# SaidasMotoresCC.net
KiCad netlist of a schematic drawn in Altium Designer
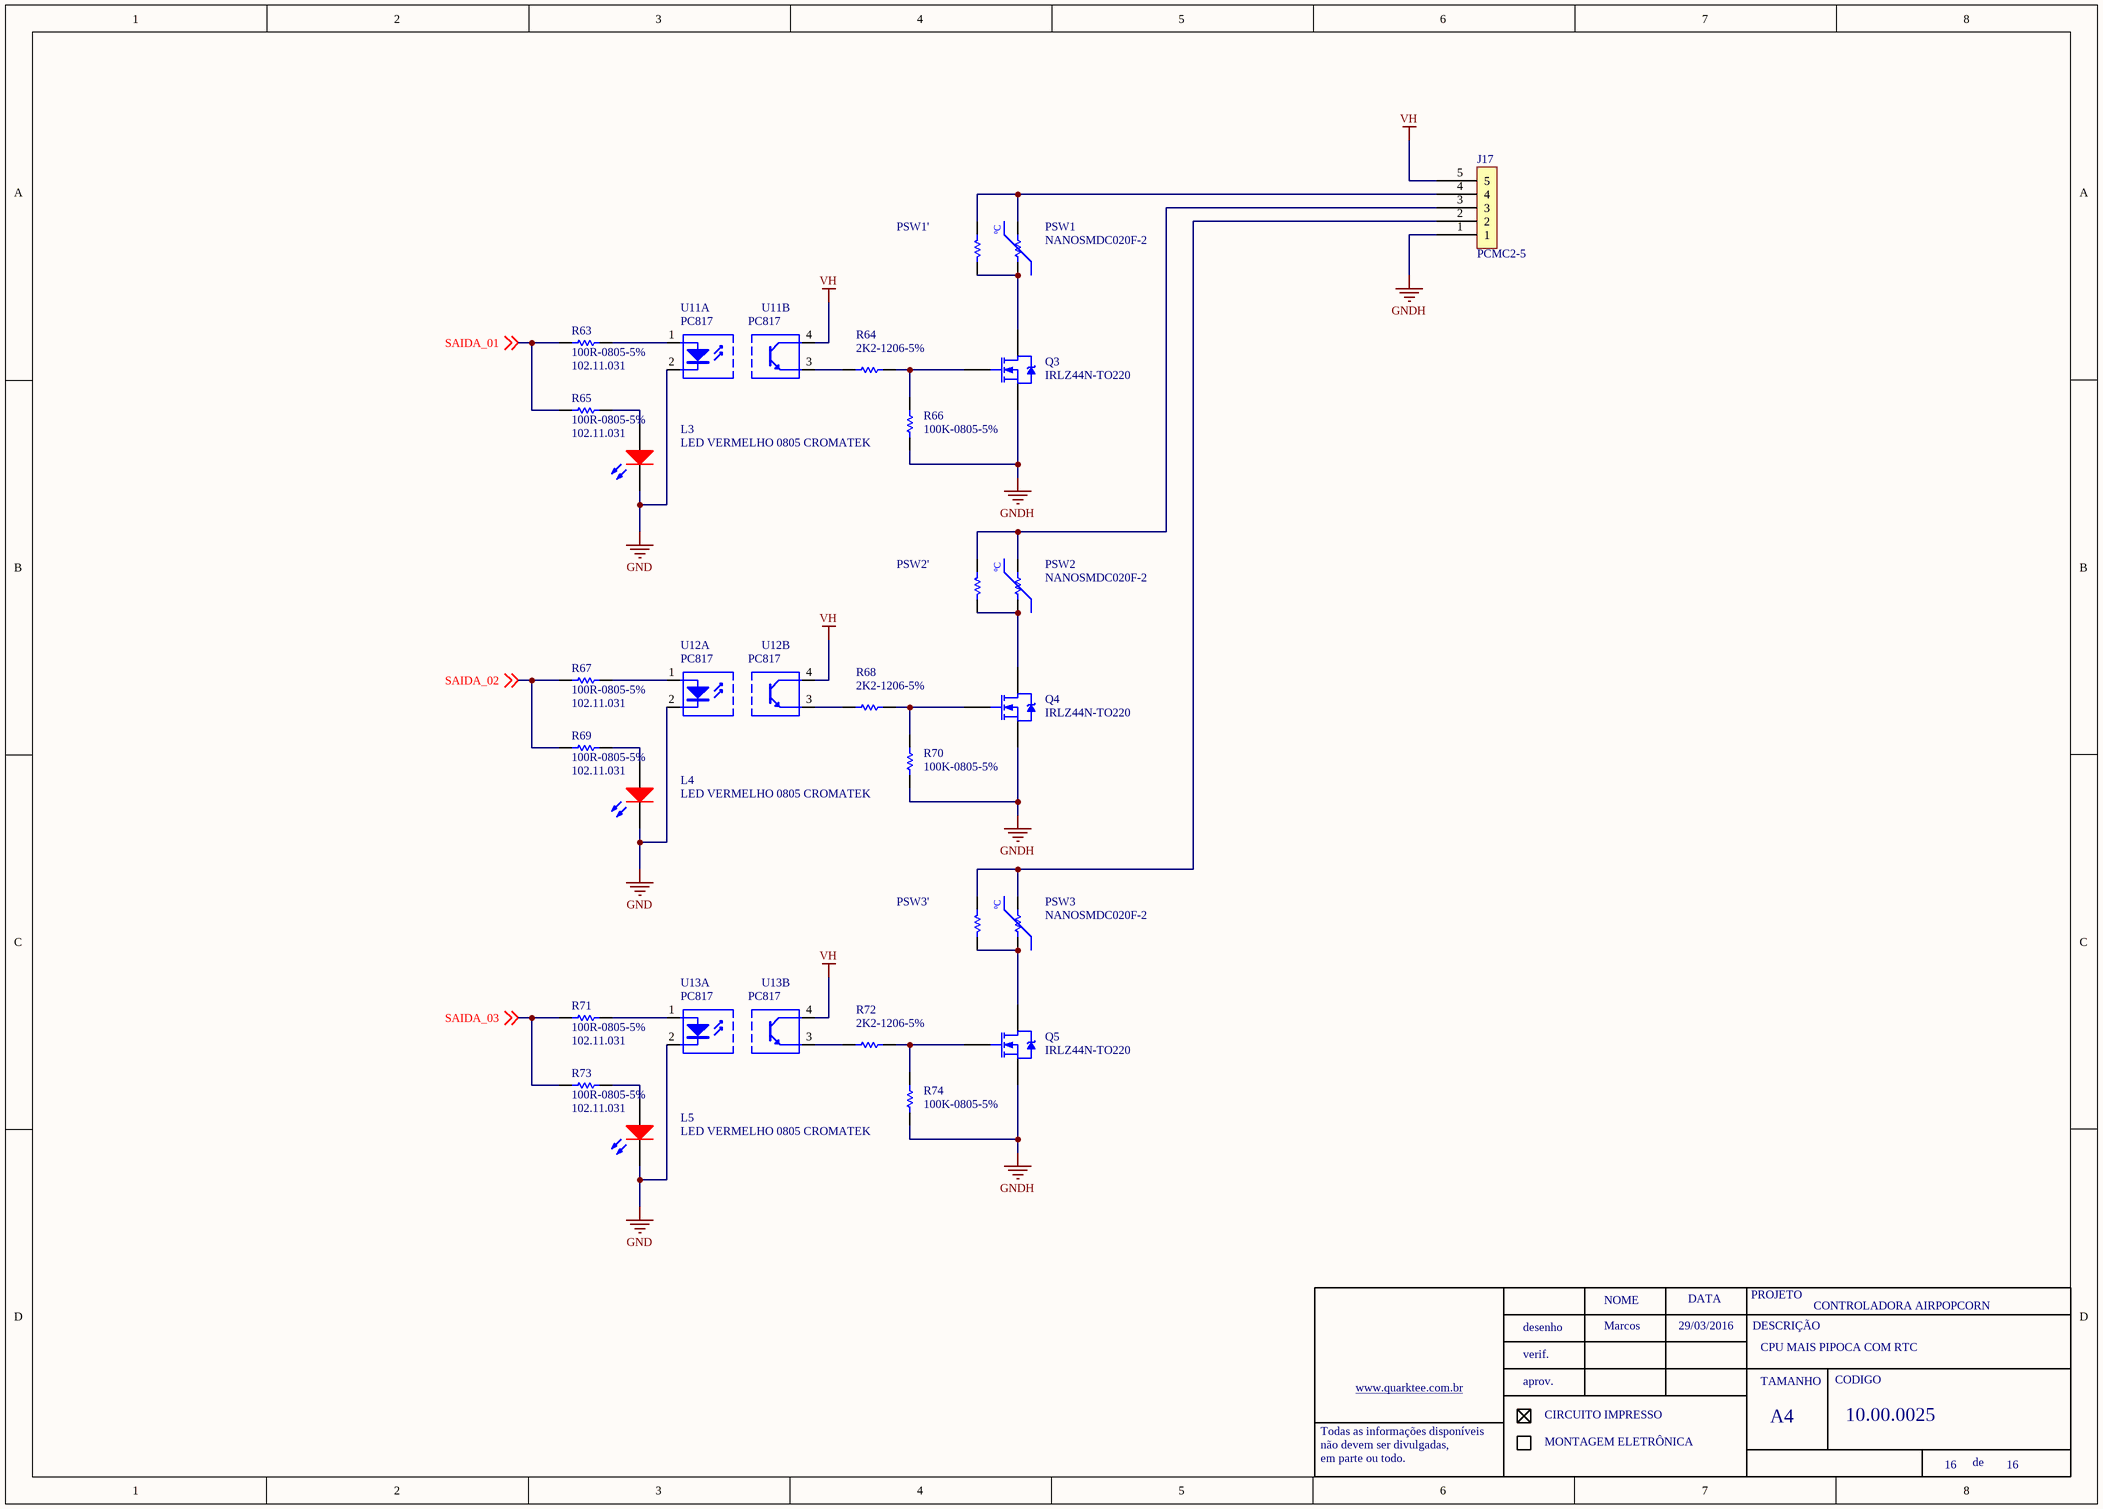
[diagram p0: SaidasMotoresCC.SchDoc]

(export (version "E")
  (design (tool "Eeschema 10.0.6"))
  (components
    (comp (ref "J17") (value "PCMC2-5") (footprint "PCMC2-5") (libsource (lib "AquinoLib") (part "PCMC2-5")))
    (comp (ref "L3")
      (value "LED VERMELHO 0805 CROMATEK")
      (footprint "LED 0805 - REVI")
      (description "LED VERMELHO 0603 SMD")
      (libsource (lib "AquinoLib") (part "LED VERMELHO 0603 SMD"))
    )
    (comp (ref "L4")
      (value "LED VERMELHO 0805 CROMATEK")
      (footprint "LED 0805 - REVI")
      (description "LED VERMELHO 0603 SMD")
      (libsource (lib "AquinoLib") (part "LED VERMELHO 0603 SMD"))
    )
    (comp (ref "L5")
      (value "LED VERMELHO 0805 CROMATEK")
      (footprint "LED 0805 - REVI")
      (description "LED VERMELHO 0603 SMD")
      (libsource (lib "AquinoLib") (part "LED VERMELHO 0603 SMD"))
    )
    (comp (ref "PSW1")
      (value "NANOSMDC020F-2")
      (footprint "2512 - REVISADO")
      (libsource (lib "AquinoLib") (part "POLYSWITCH 200mA"))
    )
    (comp (ref "PSW1'")
      (value "~")
      (footprint "1206-REVISADO O")
      (description "100K-0805-5%")
      (libsource (lib "AquinoLib") (part "100K-0805-5%"))
    )
    (comp (ref "PSW2")
      (value "NANOSMDC020F-2")
      (footprint "2512 - REVISADO")
      (libsource (lib "AquinoLib") (part "POLYSWITCH 200mA"))
    )
    (comp (ref "PSW2'")
      (value "~")
      (footprint "1206-REVISADO O")
      (description "100K-0805-5%")
      (libsource (lib "AquinoLib") (part "100K-0805-5%"))
    )
    (comp (ref "PSW3")
      (value "NANOSMDC020F-2")
      (footprint "2512 - REVISADO")
      (libsource (lib "AquinoLib") (part "POLYSWITCH 200mA"))
    )
    (comp (ref "PSW3'")
      (value "~")
      (footprint "1206-REVISADO O")
      (description "100K-0805-5%")
      (libsource (lib "AquinoLib") (part "100K-0805-5%"))
    )
    (comp (ref "Q3")
      (value "IRLZ44N-TO220")
      (footprint "TO220-3 EM PÉ")
      (libsource (lib "ChaveDigital3") (part "IRLZ44N-TO220"))
    )
    (comp (ref "Q4")
      (value "IRLZ44N-TO220")
      (footprint "TO220-3 EM PÉ")
      (libsource (lib "ChaveDigital3") (part "IRLZ44N-TO220"))
    )
    (comp (ref "Q5")
      (value "IRLZ44N-TO220")
      (footprint "TO220-3 EM PÉ")
      (libsource (lib "ChaveDigital3") (part "IRLZ44N-TO220"))
    )
    (comp (ref "R63")
      (value "100R-0805-5%")
      (footprint "0805-REVISADO O")
      (fields (field (name "ERP") "102.11.031"))
      (libsource (lib "AquinoLib") (part "100R-0805-5%"))
    )
    (comp (ref "R64")
      (value "2K2-1206-5%")
      (footprint "1206-REVISADO O")
      (description "100K-0805-5%")
      (libsource (lib "AquinoLib") (part "100K-0805-5%"))
    )
    (comp (ref "R65")
      (value "100R-0805-5%")
      (footprint "0805-REVISADO O")
      (fields (field (name "ERP") "102.11.031"))
      (libsource (lib "AquinoLib") (part "100R-0805-5%"))
    )
    (comp (ref "R66")
      (value "100K-0805-5%")
      (footprint "0805-REVISADO O")
      (libsource (lib "AquinoLib") (part "100K-0805-5%"))
    )
    (comp (ref "R67")
      (value "100R-0805-5%")
      (footprint "0805-REVISADO O")
      (fields (field (name "ERP") "102.11.031"))
      (libsource (lib "AquinoLib") (part "100R-0805-5%"))
    )
    (comp (ref "R68")
      (value "2K2-1206-5%")
      (footprint "1206-REVISADO O")
      (description "100K-0805-5%")
      (libsource (lib "AquinoLib") (part "100K-0805-5%"))
    )
    (comp (ref "R69")
      (value "100R-0805-5%")
      (footprint "0805-REVISADO O")
      (fields (field (name "ERP") "102.11.031"))
      (libsource (lib "AquinoLib") (part "100R-0805-5%"))
    )
    (comp (ref "R70")
      (value "100K-0805-5%")
      (footprint "0805-REVISADO O")
      (libsource (lib "AquinoLib") (part "100K-0805-5%"))
    )
    (comp (ref "R71")
      (value "100R-0805-5%")
      (footprint "0805-REVISADO O")
      (fields (field (name "ERP") "102.11.031"))
      (libsource (lib "AquinoLib") (part "100R-0805-5%"))
    )
    (comp (ref "R72")
      (value "2K2-1206-5%")
      (footprint "1206-REVISADO O")
      (description "100K-0805-5%")
      (libsource (lib "AquinoLib") (part "100K-0805-5%"))
    )
    (comp (ref "R73")
      (value "100R-0805-5%")
      (footprint "0805-REVISADO O")
      (fields (field (name "ERP") "102.11.031"))
      (libsource (lib "AquinoLib") (part "100R-0805-5%"))
    )
    (comp (ref "R74")
      (value "100K-0805-5%")
      (footprint "0805-REVISADO O")
      (libsource (lib "AquinoLib") (part "100K-0805-5%"))
    )
    (comp (ref "U11")
      (value "PC817")
      (footprint "DIP-4")
      (description "OPTOACOPLADOR PC817 DIP-4")
      (libsource (lib "AquinoLib") (part "PC817"))
    )
    (comp (ref "U12")
      (value "PC817")
      (footprint "DIP-4")
      (description "OPTOACOPLADOR PC817 DIP-4")
      (libsource (lib "AquinoLib") (part "PC817"))
    )
    (comp (ref "U13")
      (value "PC817")
      (footprint "DIP-4")
      (description "OPTOACOPLADOR PC817 DIP-4")
      (libsource (lib "AquinoLib") (part "PC817"))
    )
  )
  (nets
    (net (code "1") (name "GND") (class "Default")
      (node (ref "L3") (pin "2") (pinfunction "K_2") (pintype "passive"))
      (node (ref "L4") (pin "2") (pinfunction "K_2") (pintype "passive"))
      (node (ref "L5") (pin "2") (pinfunction "K_2") (pintype "passive"))
      (node (ref "U11") (pin "2") (pinfunction "K_2") (pintype "passive"))
      (node (ref "U12") (pin "2") (pinfunction "K_2") (pintype "passive"))
      (node (ref "U13") (pin "2") (pinfunction "K_2") (pintype "passive"))
    )
    (net (code "2") (name "GNDH") (class "Default")
      (node (ref "J17") (pin "1") (pinfunction "1_1") (pintype "passive"))
      (node (ref "Q3") (pin "3") (pinfunction "S_3") (pintype "passive"))
      (node (ref "Q4") (pin "3") (pinfunction "S_3") (pintype "passive"))
      (node (ref "Q5") (pin "3") (pinfunction "S_3") (pintype "passive"))
      (node (ref "R66") (pin "1") (pinfunction "1_1") (pintype "passive"))
      (node (ref "R70") (pin "1") (pinfunction "1_1") (pintype "passive"))
      (node (ref "R74") (pin "1") (pinfunction "1_1") (pintype "passive"))
    )
    (net (code "3") (name "Net-(J17-Pad2)") (class "Default")
      (node (ref "J17") (pin "2") (pinfunction "2_2") (pintype "passive"))
      (node (ref "PSW3") (pin "2") (pinfunction "2_2") (pintype "passive"))
      (node (ref "PSW3'") (pin "1") (pinfunction "1_1") (pintype "passive"))
    )
    (net (code "4") (name "Net-(J17-Pad3)") (class "Default")
      (node (ref "J17") (pin "3") (pinfunction "3_3") (pintype "passive"))
      (node (ref "PSW2") (pin "2") (pinfunction "2_2") (pintype "passive"))
      (node (ref "PSW2'") (pin "1") (pinfunction "1_1") (pintype "passive"))
    )
    (net (code "5") (name "Net-(J17-Pad4)") (class "Default")
      (node (ref "J17") (pin "4") (pinfunction "4_4") (pintype "passive"))
      (node (ref "PSW1") (pin "2") (pinfunction "2_2") (pintype "passive"))
      (node (ref "PSW1'") (pin "1") (pinfunction "1_1") (pintype "passive"))
    )
    (net (code "6") (name "Net-(L3-A)") (class "Default")
      (node (ref "L3") (pin "1") (pinfunction "A_1") (pintype "passive"))
      (node (ref "R65") (pin "2") (pinfunction "2_2") (pintype "passive"))
    )
    (net (code "7") (name "Net-(L4-A)") (class "Default")
      (node (ref "L4") (pin "1") (pinfunction "A_1") (pintype "passive"))
      (node (ref "R69") (pin "2") (pinfunction "2_2") (pintype "passive"))
    )
    (net (code "8") (name "Net-(L5-A)") (class "Default")
      (node (ref "L5") (pin "1") (pinfunction "A_1") (pintype "passive"))
      (node (ref "R73") (pin "2") (pinfunction "2_2") (pintype "passive"))
    )
    (net (code "9") (name "Net-(Q3-D)") (class "Default")
      (node (ref "PSW1") (pin "1") (pinfunction "1_1") (pintype "passive"))
      (node (ref "PSW1'") (pin "2") (pinfunction "2_2") (pintype "passive"))
      (node (ref "Q3") (pin "2") (pinfunction "D_2") (pintype "passive"))
    )
    (net (code "10") (name "Net-(Q3-G)") (class "Default")
      (node (ref "Q3") (pin "1") (pinfunction "G_1") (pintype "passive"))
      (node (ref "R64") (pin "1") (pinfunction "1_1") (pintype "passive"))
      (node (ref "R66") (pin "2") (pinfunction "2_2") (pintype "passive"))
    )
    (net (code "11") (name "Net-(Q4-D)") (class "Default")
      (node (ref "PSW2") (pin "1") (pinfunction "1_1") (pintype "passive"))
      (node (ref "PSW2'") (pin "2") (pinfunction "2_2") (pintype "passive"))
      (node (ref "Q4") (pin "2") (pinfunction "D_2") (pintype "passive"))
    )
    (net (code "12") (name "Net-(Q4-G)") (class "Default")
      (node (ref "Q4") (pin "1") (pinfunction "G_1") (pintype "passive"))
      (node (ref "R68") (pin "1") (pinfunction "1_1") (pintype "passive"))
      (node (ref "R70") (pin "2") (pinfunction "2_2") (pintype "passive"))
    )
    (net (code "13") (name "Net-(Q5-D)") (class "Default")
      (node (ref "PSW3") (pin "1") (pinfunction "1_1") (pintype "passive"))
      (node (ref "PSW3'") (pin "2") (pinfunction "2_2") (pintype "passive"))
      (node (ref "Q5") (pin "2") (pinfunction "D_2") (pintype "passive"))
    )
    (net (code "14") (name "Net-(Q5-G)") (class "Default")
      (node (ref "Q5") (pin "1") (pinfunction "G_1") (pintype "passive"))
      (node (ref "R72") (pin "1") (pinfunction "1_1") (pintype "passive"))
      (node (ref "R74") (pin "2") (pinfunction "2_2") (pintype "passive"))
    )
    (net (code "15") (name "Net-(U11A-A)") (class "Default")
      (node (ref "R63") (pin "2") (pinfunction "2_2") (pintype "passive"))
      (node (ref "U11") (pin "1") (pinfunction "A_1") (pintype "passive"))
    )
    (net (code "16") (name "Net-(U11B-E)") (class "Default")
      (node (ref "R64") (pin "2") (pinfunction "2_2") (pintype "passive"))
      (node (ref "U11") (pin "3") (pinfunction "E_3") (pintype "passive"))
    )
    (net (code "17") (name "Net-(U12A-A)") (class "Default")
      (node (ref "R67") (pin "2") (pinfunction "2_2") (pintype "passive"))
      (node (ref "U12") (pin "1") (pinfunction "A_1") (pintype "passive"))
    )
    (net (code "18") (name "Net-(U12B-E)") (class "Default")
      (node (ref "R68") (pin "2") (pinfunction "2_2") (pintype "passive"))
      (node (ref "U12") (pin "3") (pinfunction "E_3") (pintype "passive"))
    )
    (net (code "19") (name "Net-(U13A-A)") (class "Default")
      (node (ref "R71") (pin "2") (pinfunction "2_2") (pintype "passive"))
      (node (ref "U13") (pin "1") (pinfunction "A_1") (pintype "passive"))
    )
    (net (code "20") (name "Net-(U13B-E)") (class "Default")
      (node (ref "R72") (pin "2") (pinfunction "2_2") (pintype "passive"))
      (node (ref "U13") (pin "3") (pinfunction "E_3") (pintype "passive"))
    )
    (net (code "21") (name "SAIDA_01") (class "Default")
      (node (ref "R63") (pin "1") (pinfunction "1_1") (pintype "passive"))
      (node (ref "R65") (pin "1") (pinfunction "1_1") (pintype "passive"))
    )
    (net (code "22") (name "SAIDA_02") (class "Default")
      (node (ref "R67") (pin "1") (pinfunction "1_1") (pintype "passive"))
      (node (ref "R69") (pin "1") (pinfunction "1_1") (pintype "passive"))
    )
    (net (code "23") (name "SAIDA_03") (class "Default")
      (node (ref "R71") (pin "1") (pinfunction "1_1") (pintype "passive"))
      (node (ref "R73") (pin "1") (pinfunction "1_1") (pintype "passive"))
    )
    (net (code "24") (name "VH") (class "Default")
      (node (ref "J17") (pin "5") (pinfunction "5_5") (pintype "passive"))
      (node (ref "U11") (pin "4") (pinfunction "C_4") (pintype "passive"))
      (node (ref "U12") (pin "4") (pinfunction "C_4") (pintype "passive"))
      (node (ref "U13") (pin "4") (pinfunction "C_4") (pintype "passive"))
    )
  )
)
